# Sequencer-V01-009.net
KiCad netlist of a schematic drawn in EAGLE
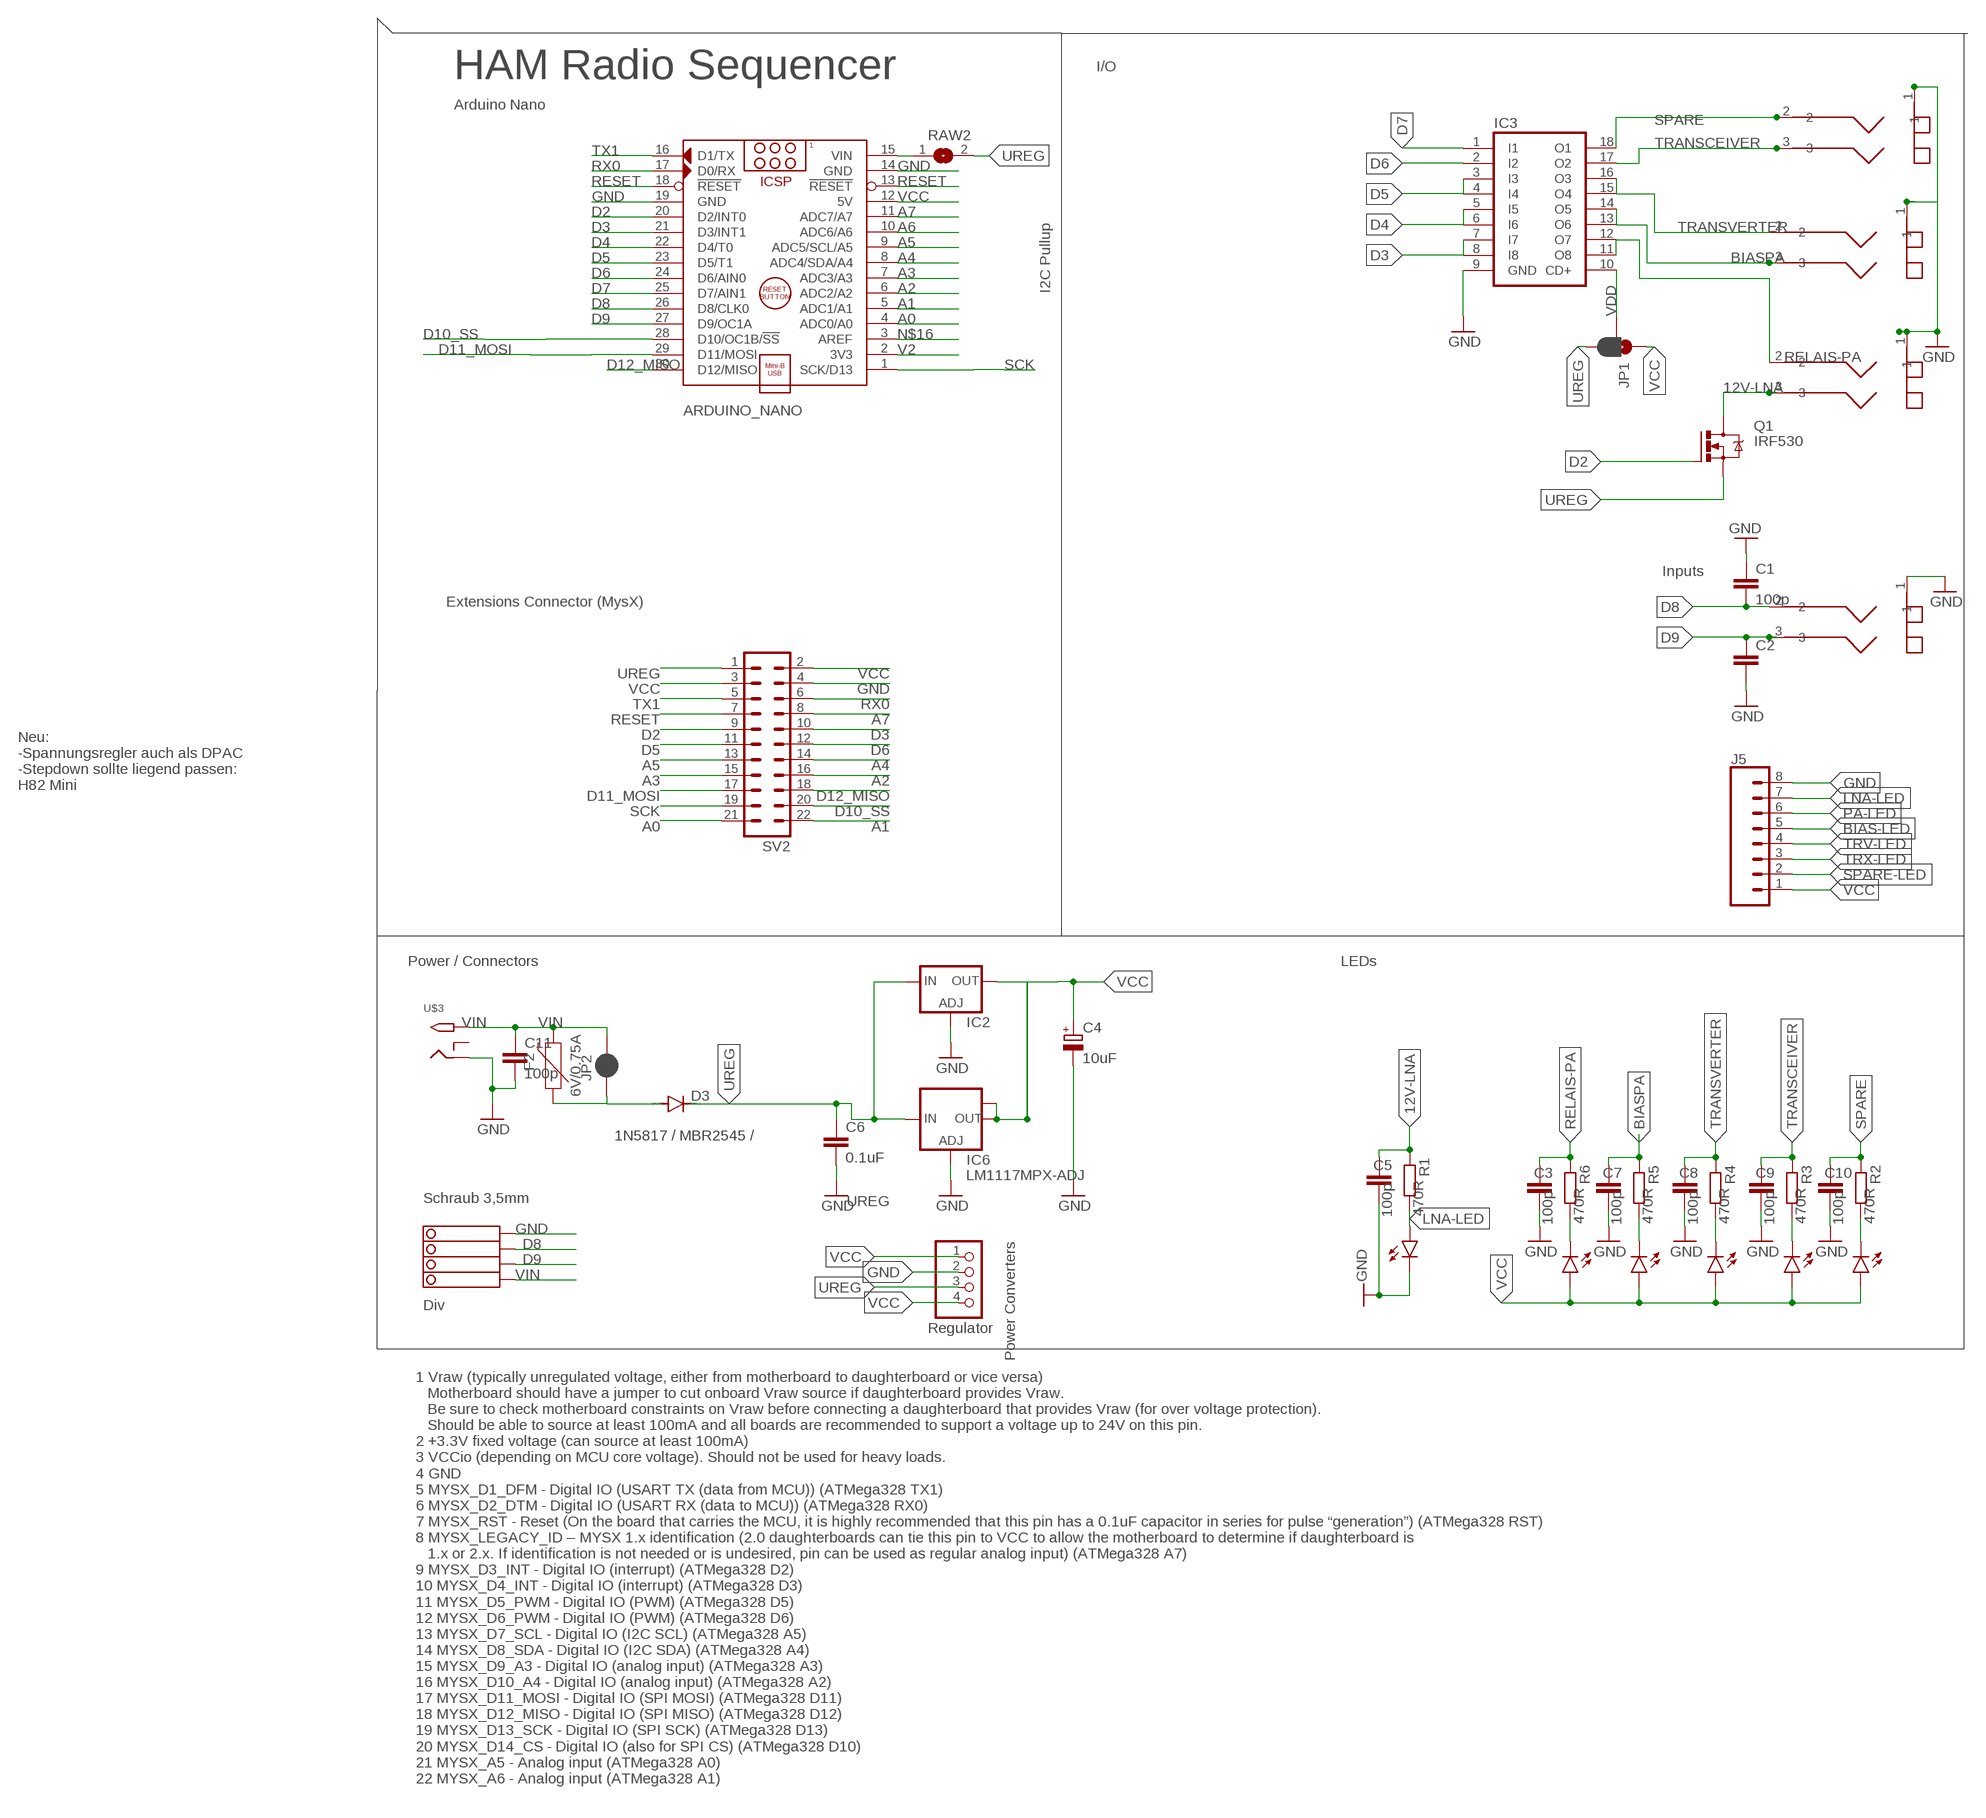
[diagram p0: schematic, sheet 1]

(export (version "E")
  (design (tool "Eeschema 10.0.6"))
  (components
    (comp (ref "ARDUINO_NANO")
      (value "ARDUINO_NANO_OHNE-BOHR")
      (footprint "eagle-import:ARDUINO_NANO")
      (libsource (lib "eagle-import") (part "ARDUINO_NANO_OHNE-BOHR"))
    )
    (comp (ref "C1")
      (value "100p")
      (footprint "eagle-import:C025-025X050")
      (libsource (lib "eagle-import") (part "C-EU025-025X050"))
    )
    (comp (ref "C2")
      (value "C-EU025-025X050")
      (footprint "eagle-import:C025-025X050")
      (libsource (lib "eagle-import") (part "C-EU025-025X050"))
    )
    (comp (ref "C3")
      (value "100p")
      (footprint "eagle-import:C025-025X050")
      (libsource (lib "eagle-import") (part "C-EU025-025X050"))
    )
    (comp (ref "C4")
      (value "10uF")
      (footprint "eagle-import:E3,5-8")
      (libsource (lib "eagle-import") (part "CPOL-EUE3.5-8"))
    )
    (comp (ref "C5")
      (value "100p")
      (footprint "eagle-import:C025-025X050")
      (libsource (lib "eagle-import") (part "C-EU025-025X050"))
    )
    (comp (ref "C6")
      (value "0.1uF")
      (footprint "eagle-import:C050-024X044")
      (libsource (lib "eagle-import") (part "C-EU050-024X044"))
    )
    (comp (ref "C7")
      (value "100p")
      (footprint "eagle-import:C025-025X050")
      (libsource (lib "eagle-import") (part "C-EU025-025X050"))
    )
    (comp (ref "C8")
      (value "100p")
      (footprint "eagle-import:C025-025X050")
      (libsource (lib "eagle-import") (part "C-EU025-025X050"))
    )
    (comp (ref "C9")
      (value "100p")
      (footprint "eagle-import:C025-025X050")
      (libsource (lib "eagle-import") (part "C-EU025-025X050"))
    )
    (comp (ref "C10")
      (value "100p")
      (footprint "eagle-import:C025-025X050")
      (libsource (lib "eagle-import") (part "C-EU025-025X050"))
    )
    (comp (ref "C11")
      (value "100p")
      (footprint "eagle-import:C025-025X050")
      (libsource (lib "eagle-import") (part "C-EU025-025X050"))
    )
    (comp (ref "D3")
      (value "1N5817 / MBR2545 /")
      (footprint "eagle-import:D-2.5")
      (libsource (lib "eagle-import") (part "DIODE-D-2.5"))
    )
    (comp (ref "F2")
      (value "6V/0.75A")
      (footprint "eagle-import:1206")
      (libsource (lib "eagle-import") (part "PPTC_THREE-QUARTER-AMP"))
    )
    (comp (ref "IC2")
      (value "LD117ADT50TR")
      (footprint "eagle-import:DPACK")
      (libsource (lib "eagle-import") (part "LD117A?DT50TR"))
    )
    (comp (ref "IC3")
      (value "ULN2803A")
      (footprint "eagle-import:DIL18")
      (libsource (lib "eagle-import") (part "ULN2803A"))
    )
    (comp (ref "IC6")
      (value "LM1117MPX-ADJ")
      (footprint "eagle-import:SOT223")
      (libsource (lib "eagle-import") (part "LM1117MPX-ADJ"))
    )
    (comp (ref "J1")
      (value "RCJ-2234")
      (footprint "eagle-import:RCJ-2221")
      (fields (field (name "MF") "CUI Devices"))
      (libsource (lib "eagle-import") (part "RCJ-2234"))
    )
    (comp (ref "J2")
      (value "RCJ-2234")
      (footprint "eagle-import:RCJ-2221")
      (fields (field (name "MF") "CUI Devices"))
      (libsource (lib "eagle-import") (part "RCJ-2234"))
    )
    (comp (ref "J3")
      (value "RCJ-2234")
      (footprint "eagle-import:RCJ-2221")
      (fields (field (name "MF") "CUI Devices"))
      (libsource (lib "eagle-import") (part "RCJ-2234"))
    )
    (comp (ref "J4")
      (value "RCJ-2234")
      (footprint "eagle-import:RCJ-2221")
      (fields (field (name "MF") "CUI Devices"))
      (libsource (lib "eagle-import") (part "RCJ-2234"))
    )
    (comp (ref "J5")
      (value "CONN_08LOCK")
      (footprint "eagle-import:1X08_LOCK")
      (libsource (lib "eagle-import") (part "CONN_08LOCK"))
    )
    (comp (ref "JP1")
      (value "JUMPER-SMT_3_1-NC_PASTE_NO-SILK")
      (footprint "eagle-import:SMT-JUMPER_3_1-NC_PASTE_NO-SILK")
      (libsource (lib "eagle-import") (part "JUMPER-SMT_3_1-NC_PASTE_NO-SILK"))
    )
    (comp (ref "JP2")
      (value "JUMPER-SMT_2_NC_PASTE_NO-SILK")
      (footprint "eagle-import:SMT-JUMPER_2_NC_PASTE_NO-SILK")
      (libsource (lib "eagle-import") (part "JUMPER-SMT_2_NC_PASTE_NO-SILK"))
    )
    (comp (ref "LED1")
      (value "LED3MM")
      (footprint "eagle-import:LED3MM")
      (libsource (lib "eagle-import") (part "LED3MM"))
    )
    (comp (ref "LED2")
      (value "LED3MM")
      (footprint "eagle-import:LED3MM")
      (libsource (lib "eagle-import") (part "LED3MM"))
    )
    (comp (ref "LED3")
      (value "LED3MM")
      (footprint "eagle-import:LED3MM")
      (libsource (lib "eagle-import") (part "LED3MM"))
    )
    (comp (ref "LED4")
      (value "LED3MM")
      (footprint "eagle-import:LED3MM")
      (libsource (lib "eagle-import") (part "LED3MM"))
    )
    (comp (ref "LED5")
      (value "LED3MM")
      (footprint "eagle-import:LED3MM")
      (libsource (lib "eagle-import") (part "LED3MM"))
    )
    (comp (ref "LED6")
      (value "LED3MM")
      (footprint "eagle-import:LED3MM")
      (libsource (lib "eagle-import") (part "LED3MM"))
    )
    (comp (ref "Q1")
      (value "IRF530")
      (footprint "eagle-import:TO220BV")
      (libsource (lib "eagle-import") (part "IRF530"))
    )
    (comp (ref "R1")
      (value "470R")
      (footprint "eagle-import:0204_5")
      (libsource (lib "eagle-import") (part "R-EU_0204/5"))
    )
    (comp (ref "R2")
      (value "470R")
      (footprint "eagle-import:0204_5")
      (libsource (lib "eagle-import") (part "R-EU_0204/5"))
    )
    (comp (ref "R3")
      (value "470R")
      (footprint "eagle-import:0204_5")
      (libsource (lib "eagle-import") (part "R-EU_0204/5"))
    )
    (comp (ref "R4")
      (value "470R")
      (footprint "eagle-import:0204_5")
      (libsource (lib "eagle-import") (part "R-EU_0204/5"))
    )
    (comp (ref "R5")
      (value "470R")
      (footprint "eagle-import:0204_5")
      (libsource (lib "eagle-import") (part "R-EU_0204/5"))
    )
    (comp (ref "R6")
      (value "470R")
      (footprint "eagle-import:0204_5")
      (libsource (lib "eagle-import") (part "R-EU_0204/5"))
    )
    (comp (ref "RAW2")
      (value "SJ")
      (footprint "eagle-import:SJ")
      (libsource (lib "eagle-import") (part "SJ"))
    )
    (comp (ref "STEPDWN")
      (value "PINHD-1X04_2.54-S")
      (footprint "eagle-import:1X04-S")
      (libsource (lib "eagle-import") (part "PINHD-1X04_2.54-S"))
    )
    (comp (ref "SV2")
      (value "MA11-2")
      (footprint "eagle-import:MA11-2")
      (libsource (lib "eagle-import") (part "MA11-2"))
    )
    (comp (ref "U$3")
      (value "2.1MMJACKTHM")
      (footprint "eagle-import:PJ-102A")
      (libsource (lib "eagle-import") (part "2.1MMJACKTHM"))
    )
    (comp (ref "X4")
      (value "1751264")
      (footprint "eagle-import:1751264")
      (libsource (lib "eagle-import") (part "1751264"))
    )
  )
  (nets
    (net (code "1") (name "/A0") (class "Default")
      (node (ref "ARDUINO_NANO") (pin "4") (pinfunction "ADC0/A0_4") (pintype "bidirectional"))
      (node (ref "SV2") (pin "21") (pinfunction "21_21") (pintype "passive"))
    )
    (net (code "2") (name "/A1") (class "Default")
      (node (ref "ARDUINO_NANO") (pin "5") (pinfunction "ADC1/A1_5") (pintype "bidirectional"))
      (node (ref "SV2") (pin "22") (pinfunction "22_22") (pintype "passive"))
    )
    (net (code "3") (name "/A2") (class "Default")
      (node (ref "ARDUINO_NANO") (pin "6") (pinfunction "ADC2/A2_6") (pintype "bidirectional"))
      (node (ref "SV2") (pin "16") (pinfunction "16_16") (pintype "passive"))
    )
    (net (code "4") (name "/A3") (class "Default")
      (node (ref "ARDUINO_NANO") (pin "7") (pinfunction "ADC3/A3_7") (pintype "bidirectional"))
      (node (ref "SV2") (pin "15") (pinfunction "15_15") (pintype "passive"))
    )
    (net (code "5") (name "/A4") (class "Default")
      (node (ref "ARDUINO_NANO") (pin "8") (pinfunction "ADC4/SDA/A4_8") (pintype "bidirectional"))
      (node (ref "SV2") (pin "14") (pinfunction "14_14") (pintype "passive"))
    )
    (net (code "6") (name "/A5") (class "Default")
      (node (ref "ARDUINO_NANO") (pin "9") (pinfunction "ADC5/SCL/A5_9") (pintype "bidirectional"))
      (node (ref "SV2") (pin "13") (pinfunction "13_13") (pintype "passive"))
    )
    (net (code "7") (name "/A6") (class "Default")
      (node (ref "ARDUINO_NANO") (pin "10") (pinfunction "ADC6/A6_10") (pintype "bidirectional"))
    )
    (net (code "8") (name "/A7") (class "Default")
      (node (ref "ARDUINO_NANO") (pin "11") (pinfunction "ADC7/A7_11") (pintype "bidirectional"))
      (node (ref "SV2") (pin "8") (pinfunction "8_8") (pintype "passive"))
    )
    (net (code "9") (name "/D10_SS") (class "Default")
      (node (ref "ARDUINO_NANO") (pin "28") (pinfunction "D10/OC1B/~{SS}_28") (pintype "bidirectional"))
      (node (ref "SV2") (pin "20") (pinfunction "20_20") (pintype "passive"))
    )
    (net (code "10") (name "/D11_MOSI") (class "Default")
      (node (ref "ARDUINO_NANO") (pin "29") (pinfunction "D11/MOSI_29") (pintype "bidirectional"))
      (node (ref "SV2") (pin "17") (pinfunction "17_17") (pintype "passive"))
    )
    (net (code "11") (name "/D12_MISO") (class "Default")
      (node (ref "ARDUINO_NANO") (pin "30") (pinfunction "D12/MISO_30") (pintype "bidirectional"))
      (node (ref "SV2") (pin "18") (pinfunction "18_18") (pintype "passive"))
    )
    (net (code "12") (name "/N$16") (class "Default")
      (node (ref "ARDUINO_NANO") (pin "3") (pinfunction "AREF_3") (pintype "input"))
    )
    (net (code "13") (name "/RESET") (class "Default")
      (node (ref "ARDUINO_NANO") (pin "13") (pinfunction "~{RESET}_13") (pintype "input"))
      (node (ref "ARDUINO_NANO") (pin "18") (pinfunction "~{RESET}_18") (pintype "input"))
      (node (ref "SV2") (pin "7") (pinfunction "7_7") (pintype "passive"))
    )
    (net (code "14") (name "/RX0") (class "Default")
      (node (ref "ARDUINO_NANO") (pin "17") (pinfunction "D0/RX_17") (pintype "bidirectional"))
      (node (ref "SV2") (pin "6") (pinfunction "6_6") (pintype "passive"))
    )
    (net (code "15") (name "/SCK") (class "Default")
      (node (ref "ARDUINO_NANO") (pin "1") (pinfunction "SCK/D13_1") (pintype "bidirectional"))
      (node (ref "SV2") (pin "19") (pinfunction "19_19") (pintype "passive"))
    )
    (net (code "16") (name "/TX1") (class "Default")
      (node (ref "ARDUINO_NANO") (pin "16") (pinfunction "D1/TX_16") (pintype "bidirectional"))
      (node (ref "SV2") (pin "5") (pinfunction "5_5") (pintype "passive"))
    )
    (net (code "17") (name "/V2") (class "Default")
      (node (ref "ARDUINO_NANO") (pin "2") (pinfunction "3V3_2") (pintype "output"))
    )
    (net (code "18") (name "/VDD") (class "Default")
      (node (ref "IC3") (pin "10") (pinfunction "CD+_10") (pintype "passive"))
      (node (ref "JP1") (pin "2") (pinfunction "2_2") (pintype "passive"))
    )
    (net (code "19") (name "/VIN") (class "Default")
      (node (ref "C11") (pin "1") (pinfunction "1_1") (pintype "passive"))
      (node (ref "F2") (pin "2") (pinfunction "2_2") (pintype "bidirectional"))
      (node (ref "JP2") (pin "2") (pinfunction "2_2") (pintype "passive"))
      (node (ref "U$3") (pin "TIP") (pinfunction "TIP_TIP") (pintype "bidirectional"))
      (node (ref "X4") (pin "1") (pinfunction "K_1") (pintype "passive"))
    )
    (net (code "20") (name "12V-LNA") (class "Default")
      (node (ref "C5") (pin "1") (pinfunction "1_1") (pintype "passive"))
      (node (ref "J3") (pin "3") (pinfunction "3_3") (pintype "bidirectional"))
      (node (ref "Q1") (pin "D") (pinfunction "D_D") (pintype "passive"))
      (node (ref "R1") (pin "1") (pinfunction "1_1") (pintype "passive"))
    )
    (net (code "21") (name "BIAS-LED") (class "Default")
      (node (ref "J5") (pin "5") (pinfunction "5_5") (pintype "passive"))
      (node (ref "LED5") (pin "K") (pinfunction "C_K") (pintype "passive"))
      (node (ref "R5") (pin "2") (pinfunction "2_2") (pintype "passive"))
    )
    (net (code "22") (name "BIASPA") (class "Default")
      (node (ref "C7") (pin "1") (pinfunction "1_1") (pintype "passive"))
      (node (ref "IC3") (pin "13") (pinfunction "O6_13") (pintype "open_collector"))
      (node (ref "IC3") (pin "14") (pinfunction "O5_14") (pintype "open_collector"))
      (node (ref "J2") (pin "3") (pinfunction "3_3") (pintype "bidirectional"))
      (node (ref "R5") (pin "1") (pinfunction "1_1") (pintype "passive"))
    )
    (net (code "23") (name "D2") (class "Default")
      (node (ref "ARDUINO_NANO") (pin "20") (pinfunction "D2/INT0_20") (pintype "bidirectional"))
      (node (ref "Q1") (pin "G") (pinfunction "G_G") (pintype "passive"))
      (node (ref "SV2") (pin "9") (pinfunction "9_9") (pintype "passive"))
    )
    (net (code "24") (name "D3") (class "Default")
      (node (ref "ARDUINO_NANO") (pin "21") (pinfunction "D3/INT1_21") (pintype "bidirectional"))
      (node (ref "IC3") (pin "7") (pinfunction "I7_7") (pintype "input"))
      (node (ref "IC3") (pin "8") (pinfunction "I8_8") (pintype "input"))
      (node (ref "SV2") (pin "10") (pinfunction "10_10") (pintype "passive"))
    )
    (net (code "25") (name "D4") (class "Default")
      (node (ref "ARDUINO_NANO") (pin "22") (pinfunction "D4/T0_22") (pintype "bidirectional"))
      (node (ref "IC3") (pin "5") (pinfunction "I5_5") (pintype "input"))
      (node (ref "IC3") (pin "6") (pinfunction "I6_6") (pintype "input"))
    )
    (net (code "26") (name "D5") (class "Default")
      (node (ref "ARDUINO_NANO") (pin "23") (pinfunction "D5/T1_23") (pintype "bidirectional"))
      (node (ref "IC3") (pin "3") (pinfunction "I3_3") (pintype "input"))
      (node (ref "IC3") (pin "4") (pinfunction "I4_4") (pintype "input"))
      (node (ref "SV2") (pin "11") (pinfunction "11_11") (pintype "passive"))
    )
    (net (code "27") (name "D6") (class "Default")
      (node (ref "ARDUINO_NANO") (pin "24") (pinfunction "D6/AIN0_24") (pintype "bidirectional"))
      (node (ref "IC3") (pin "2") (pinfunction "I2_2") (pintype "input"))
      (node (ref "SV2") (pin "12") (pinfunction "12_12") (pintype "passive"))
    )
    (net (code "28") (name "D7") (class "Default")
      (node (ref "ARDUINO_NANO") (pin "25") (pinfunction "D7/AIN1_25") (pintype "bidirectional"))
      (node (ref "IC3") (pin "1") (pinfunction "I1_1") (pintype "input"))
    )
    (net (code "29") (name "D8") (class "Default")
      (node (ref "ARDUINO_NANO") (pin "26") (pinfunction "D8/CLK0_26") (pintype "bidirectional"))
      (node (ref "C1") (pin "2") (pinfunction "2_2") (pintype "passive"))
      (node (ref "J4") (pin "2") (pinfunction "2_2") (pintype "bidirectional"))
      (node (ref "X4") (pin "3") (pinfunction "K_3") (pintype "passive"))
    )
    (net (code "30") (name "D9") (class "Default")
      (node (ref "ARDUINO_NANO") (pin "27") (pinfunction "D9/OC1A_27") (pintype "bidirectional"))
      (node (ref "C2") (pin "1") (pinfunction "1_1") (pintype "passive"))
      (node (ref "J4") (pin "3") (pinfunction "3_3") (pintype "bidirectional"))
      (node (ref "X4") (pin "2") (pinfunction "K_2") (pintype "passive"))
    )
    (net (code "31") (name "GND") (class "Default")
      (node (ref "ARDUINO_NANO") (pin "14") (pinfunction "GND_14") (pintype "power_in"))
      (node (ref "ARDUINO_NANO") (pin "19") (pinfunction "GND_19") (pintype "power_in"))
      (node (ref "C1") (pin "1") (pinfunction "1_1") (pintype "passive"))
      (node (ref "C10") (pin "2") (pinfunction "2_2") (pintype "passive"))
      (node (ref "C11") (pin "2") (pinfunction "2_2") (pintype "passive"))
      (node (ref "C2") (pin "2") (pinfunction "2_2") (pintype "passive"))
      (node (ref "C3") (pin "2") (pinfunction "2_2") (pintype "passive"))
      (node (ref "C4") (pin "-") (pinfunction "-_-") (pintype "passive"))
      (node (ref "C5") (pin "2") (pinfunction "2_2") (pintype "passive"))
      (node (ref "C6") (pin "2") (pinfunction "2_2") (pintype "passive"))
      (node (ref "C7") (pin "2") (pinfunction "2_2") (pintype "passive"))
      (node (ref "C8") (pin "2") (pinfunction "2_2") (pintype "passive"))
      (node (ref "C9") (pin "2") (pinfunction "2_2") (pintype "passive"))
      (node (ref "IC2") (pin "1") (pinfunction "ADJ_1") (pintype "input"))
      (node (ref "IC3") (pin "9") (pinfunction "GND_9") (pintype "power_in"))
      (node (ref "IC6") (pin "1") (pinfunction "ADJ_1") (pintype "input"))
      (node (ref "J1") (pin "1") (pinfunction "1_1") (pintype "bidirectional"))
      (node (ref "J2") (pin "1") (pinfunction "1_1") (pintype "bidirectional"))
      (node (ref "J3") (pin "1") (pinfunction "1_1") (pintype "bidirectional"))
      (node (ref "J4") (pin "1") (pinfunction "1_1") (pintype "bidirectional"))
      (node (ref "J5") (pin "8") (pinfunction "8_8") (pintype "passive"))
      (node (ref "LED1") (pin "K") (pinfunction "C_K") (pintype "passive"))
      (node (ref "STEPDWN") (pin "2") (pinfunction "2_2") (pintype "passive"))
      (node (ref "SV2") (pin "4") (pinfunction "4_4") (pintype "passive"))
      (node (ref "U$3") (pin "RING") (pinfunction "RING_RING") (pintype "bidirectional"))
      (node (ref "X4") (pin "4") (pinfunction "K_4") (pintype "passive"))
    )
    (net (code "32") (name "LNA-LED") (class "Default")
      (node (ref "J5") (pin "7") (pinfunction "7_7") (pintype "passive"))
      (node (ref "LED1") (pin "A") (pinfunction "A_A") (pintype "passive"))
      (node (ref "R1") (pin "2") (pinfunction "2_2") (pintype "passive"))
    )
    (net (code "33") (name "Net-(ARDUINO_NANO-VIN)") (class "Default")
      (node (ref "ARDUINO_NANO") (pin "15") (pinfunction "VIN_15") (pintype "power_in"))
      (node (ref "RAW2") (pin "1") (pinfunction "1_1") (pintype "passive"))
    )
    (net (code "34") (name "Net-(D3-PadA)") (class "Default")
      (node (ref "D3") (pin "A") (pinfunction "A_A") (pintype "passive"))
      (node (ref "F2") (pin "1") (pinfunction "1_1") (pintype "bidirectional"))
      (node (ref "JP2") (pin "1") (pinfunction "1_1") (pintype "passive"))
    )
    (net (code "35") (name "PA-LED") (class "Default")
      (node (ref "J5") (pin "6") (pinfunction "6_6") (pintype "passive"))
      (node (ref "LED6") (pin "K") (pinfunction "C_K") (pintype "passive"))
      (node (ref "R6") (pin "2") (pinfunction "2_2") (pintype "passive"))
    )
    (net (code "36") (name "RELAIS-PA") (class "Default")
      (node (ref "C3") (pin "1") (pinfunction "1_1") (pintype "passive"))
      (node (ref "IC3") (pin "11") (pinfunction "O8_11") (pintype "open_collector"))
      (node (ref "IC3") (pin "12") (pinfunction "O7_12") (pintype "open_collector"))
      (node (ref "J3") (pin "2") (pinfunction "2_2") (pintype "bidirectional"))
      (node (ref "R6") (pin "1") (pinfunction "1_1") (pintype "passive"))
    )
    (net (code "37") (name "SPARE") (class "Default")
      (node (ref "C10") (pin "1") (pinfunction "1_1") (pintype "passive"))
      (node (ref "IC3") (pin "18") (pinfunction "O1_18") (pintype "open_collector"))
      (node (ref "J1") (pin "2") (pinfunction "2_2") (pintype "bidirectional"))
      (node (ref "R2") (pin "1") (pinfunction "1_1") (pintype "passive"))
    )
    (net (code "38") (name "SPARE-LED") (class "Default")
      (node (ref "J5") (pin "2") (pinfunction "2_2") (pintype "passive"))
      (node (ref "LED2") (pin "K") (pinfunction "C_K") (pintype "passive"))
      (node (ref "R2") (pin "2") (pinfunction "2_2") (pintype "passive"))
    )
    (net (code "39") (name "TRANSCEIVER") (class "Default")
      (node (ref "C9") (pin "1") (pinfunction "1_1") (pintype "passive"))
      (node (ref "IC3") (pin "17") (pinfunction "O2_17") (pintype "open_collector"))
      (node (ref "J1") (pin "3") (pinfunction "3_3") (pintype "bidirectional"))
      (node (ref "R3") (pin "1") (pinfunction "1_1") (pintype "passive"))
    )
    (net (code "40") (name "TRANSVERTER") (class "Default")
      (node (ref "C8") (pin "1") (pinfunction "1_1") (pintype "passive"))
      (node (ref "IC3") (pin "15") (pinfunction "O4_15") (pintype "open_collector"))
      (node (ref "IC3") (pin "16") (pinfunction "O3_16") (pintype "open_collector"))
      (node (ref "J2") (pin "2") (pinfunction "2_2") (pintype "bidirectional"))
      (node (ref "R4") (pin "1") (pinfunction "1_1") (pintype "passive"))
    )
    (net (code "41") (name "TRV-LED") (class "Default")
      (node (ref "J5") (pin "4") (pinfunction "4_4") (pintype "passive"))
      (node (ref "LED4") (pin "K") (pinfunction "C_K") (pintype "passive"))
      (node (ref "R4") (pin "2") (pinfunction "2_2") (pintype "passive"))
    )
    (net (code "42") (name "TRX-LED") (class "Default")
      (node (ref "J5") (pin "3") (pinfunction "3_3") (pintype "passive"))
      (node (ref "LED3") (pin "K") (pinfunction "C_K") (pintype "passive"))
      (node (ref "R3") (pin "2") (pinfunction "2_2") (pintype "passive"))
    )
    (net (code "43") (name "UREG") (class "Default")
      (node (ref "C6") (pin "1") (pinfunction "1_1") (pintype "passive"))
      (node (ref "D3") (pin "C") (pinfunction "C_C") (pintype "passive"))
      (node (ref "IC2") (pin "3") (pinfunction "IN_3") (pintype "input"))
      (node (ref "IC6") (pin "3") (pinfunction "IN_3") (pintype "input"))
      (node (ref "JP1") (pin "3") (pinfunction "3_3") (pintype "passive"))
      (node (ref "Q1") (pin "S") (pinfunction "S_S") (pintype "passive"))
      (node (ref "RAW2") (pin "2") (pinfunction "2_2") (pintype "passive"))
      (node (ref "STEPDWN") (pin "3") (pinfunction "3_3") (pintype "passive"))
      (node (ref "SV2") (pin "1") (pinfunction "1_1") (pintype "passive"))
    )
    (net (code "44") (name "VCC") (class "Default")
      (node (ref "ARDUINO_NANO") (pin "12") (pinfunction "5V_12") (pintype "power_in"))
      (node (ref "C4") (pin "+") (pinfunction "+_+") (pintype "passive"))
      (node (ref "IC2") (pin "4") (pinfunction "OUT_4") (pintype "passive"))
      (node (ref "IC6") (pin "2") (pinfunction "OUT_2") (pintype "passive"))
      (node (ref "IC6") (pin "TAB") (pinfunction "OUT1_TAB") (pintype "passive"))
      (node (ref "J5") (pin "1") (pinfunction "1_1") (pintype "passive"))
      (node (ref "JP1") (pin "1") (pinfunction "1_1") (pintype "passive"))
      (node (ref "LED2") (pin "A") (pinfunction "A_A") (pintype "passive"))
      (node (ref "LED3") (pin "A") (pinfunction "A_A") (pintype "passive"))
      (node (ref "LED4") (pin "A") (pinfunction "A_A") (pintype "passive"))
      (node (ref "LED5") (pin "A") (pinfunction "A_A") (pintype "passive"))
      (node (ref "LED6") (pin "A") (pinfunction "A_A") (pintype "passive"))
      (node (ref "STEPDWN") (pin "1") (pinfunction "1_1") (pintype "passive"))
      (node (ref "STEPDWN") (pin "4") (pinfunction "4_4") (pintype "passive"))
      (node (ref "SV2") (pin "2") (pinfunction "2_2") (pintype "passive"))
      (node (ref "SV2") (pin "3") (pinfunction "3_3") (pintype "passive"))
    )
    (net (code "45") (name "unconnected-(U$3-PadRING_SW)") (class "Default")
      (node (ref "U$3") (pin "RING_SW") (pinfunction "RING_SW_RING_SW") (pintype "bidirectional"))
    )
  )
)
